# AutoToolZeroProbe.net
KiCad netlist of a schematic drawn in Altium Designer
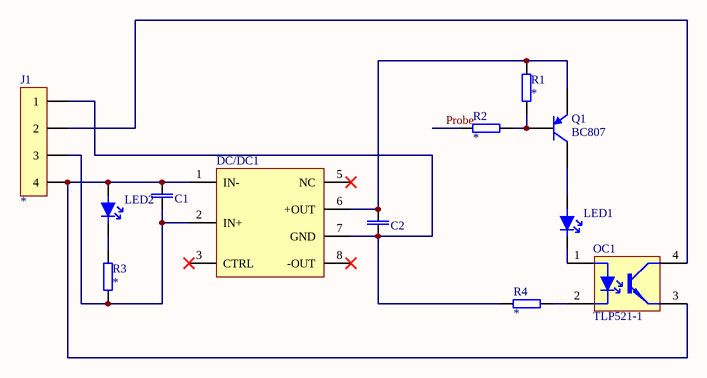
[diagram p0: AutoToolZeroProbe.SchDoc]

(export (version "E")
  (design (tool "Eeschema 10.0.6"))
  (components
    (comp (ref "C1")
      (value "~")
      (footprint "CAP 0805")
      (description "NON POLARIZED CAPACITOR")
      (libsource (lib "sajatSCH") (part "CAP"))
    )
    (comp (ref "C2")
      (value "~")
      (footprint "CAP 0805")
      (description "NON POLARIZED CAPACITOR")
      (libsource (lib "sajatSCH") (part "CAP"))
    )
    (comp (ref "DC/DC1")
      (value "~")
      (footprint "EC2SA")
      (description "2W DC-DC CONVERTER")
      (libsource (lib "sajatSCH") (part "EC2SA"))
    )
    (comp (ref "J1")
      (value "*")
      (footprint "SIL4")
      (description "4 PIN HEADER")
      (libsource (lib "sajatSCH") (part "HEADER4"))
    )
    (comp (ref "LED1")
      (value "~")
      (footprint "LED3G")
      (description "SMD, 0805 LED")
      (libsource (lib "sajatSCH") (part "LED"))
    )
    (comp (ref "LED2")
      (value "~")
      (footprint "LED3G")
      (description "SMD, 0805 LED")
      (libsource (lib "sajatSCH") (part "LED"))
    )
    (comp (ref "OC1")
      (value "TLP521-1")
      (footprint "SOP4L")
      (description "photocoupler")
      (libsource (lib "sajatSCH") (part "TLP521"))
    )
    (comp (ref "Q1")
      (value "BC807")
      (footprint "FP_SOT23-3")
      (description "PNP Transistor")
      (libsource (lib "sajatSCH") (part "BC807"))
    )
    (comp (ref "R1")
      (value "*")
      (footprint "RES 0805")
      (description "RESISTOR")
      (libsource (lib "") (part "RES_1"))
    )
    (comp (ref "R2")
      (value "*")
      (footprint "RES 0805")
      (description "RESISTOR")
      (libsource (lib "") (part "RES_2"))
    )
    (comp (ref "R3")
      (value "*")
      (footprint "RES 0805")
      (description "RESISTOR")
      (libsource (lib "") (part "RES_1"))
    )
    (comp (ref "R4")
      (value "*")
      (footprint "RES 0805")
      (description "RESISTOR")
      (libsource (lib "sajatSCH") (part "RES"))
    )
  )
  (nets
    (net (code "1") (name "/Probe") (class "Default")
      (node (ref "R2") (pin "1") (pinfunction "1_1") (pintype "passive"))
    )
    (net (code "2") (name "Net-(DC/DC1-+OUT)") (class "Default")
      (node (ref "C2") (pin "2") (pinfunction "2_2") (pintype "passive"))
      (node (ref "DC/DC1") (pin "6") (pinfunction "+OUT_6") (pintype "passive"))
      (node (ref "Q1") (pin "1") (pinfunction "E_1") (pintype "passive"))
      (node (ref "R1") (pin "2") (pinfunction "2_2") (pintype "passive"))
    )
    (net (code "3") (name "Net-(DC/DC1-GND)") (class "Default")
      (node (ref "C2") (pin "1") (pinfunction "1_1") (pintype "passive"))
      (node (ref "DC/DC1") (pin "7") (pinfunction "GND_7") (pintype "passive"))
      (node (ref "J1") (pin "1") (pinfunction "1_1") (pintype "passive"))
      (node (ref "R4") (pin "2") (pinfunction "2_2") (pintype "passive"))
    )
    (net (code "4") (name "Net-(DC/DC1-IN+)") (class "Default")
      (node (ref "C1") (pin "1") (pinfunction "1_1") (pintype "passive"))
      (node (ref "DC/DC1") (pin "2") (pinfunction "IN+_2") (pintype "passive"))
      (node (ref "J1") (pin "3") (pinfunction "3_3") (pintype "passive"))
      (node (ref "R3") (pin "1") (pinfunction "1_1") (pintype "passive"))
    )
    (net (code "5") (name "Net-(DC/DC1-IN-)") (class "Default")
      (node (ref "C1") (pin "2") (pinfunction "2_2") (pintype "passive"))
      (node (ref "DC/DC1") (pin "1") (pinfunction "IN-_1") (pintype "passive"))
      (node (ref "J1") (pin "4") (pinfunction "4_4") (pintype "passive"))
      (node (ref "LED2") (pin "1") (pinfunction "A_1") (pintype "passive"))
      (node (ref "OC1") (pin "3") (pinfunction "E_3") (pintype "passive"))
    )
    (net (code "6") (name "Net-(LED1-A)") (class "Default")
      (node (ref "LED1") (pin "1") (pinfunction "A_1") (pintype "passive"))
      (node (ref "Q1") (pin "3") (pinfunction "C_3") (pintype "passive"))
    )
    (net (code "7") (name "Net-(LED1-K)") (class "Default")
      (node (ref "LED1") (pin "2") (pinfunction "K_2") (pintype "passive"))
      (node (ref "OC1") (pin "1") (pinfunction "A_1") (pintype "passive"))
    )
    (net (code "8") (name "Net-(LED2-K)") (class "Default")
      (node (ref "LED2") (pin "2") (pinfunction "K_2") (pintype "passive"))
      (node (ref "R3") (pin "2") (pinfunction "2_2") (pintype "passive"))
    )
    (net (code "9") (name "Net-(OC1-C)") (class "Default")
      (node (ref "J1") (pin "2") (pinfunction "2_2") (pintype "passive"))
      (node (ref "OC1") (pin "4") (pinfunction "C_4") (pintype "passive"))
    )
    (net (code "10") (name "Net-(OC1-K)") (class "Default")
      (node (ref "OC1") (pin "2") (pinfunction "K_2") (pintype "passive"))
      (node (ref "R4") (pin "1") (pinfunction "1_1") (pintype "passive"))
    )
    (net (code "11") (name "Net-(Q1-B)") (class "Default")
      (node (ref "Q1") (pin "2") (pinfunction "B_2") (pintype "passive"))
      (node (ref "R1") (pin "1") (pinfunction "1_1") (pintype "passive"))
      (node (ref "R2") (pin "2") (pinfunction "2_2") (pintype "passive"))
    )
    (net (code "12") (name "unconnected-(DC/DC1--OUT-Pad8)") (class "Default")
      (node (ref "DC/DC1") (pin "8") (pinfunction "-OUT_8") (pintype "passive+no_connect"))
    )
    (net (code "13") (name "unconnected-(DC/DC1-CTRL-Pad3)") (class "Default")
      (node (ref "DC/DC1") (pin "3") (pinfunction "CTRL_3") (pintype "passive+no_connect"))
    )
    (net (code "14") (name "unconnected-(DC/DC1-NC-Pad5)") (class "Default")
      (node (ref "DC/DC1") (pin "5") (pinfunction "NC_5") (pintype "passive+no_connect"))
    )
  )
)
